# Breakout_05_08.net
KiCad netlist of a schematic drawn in EAGLE
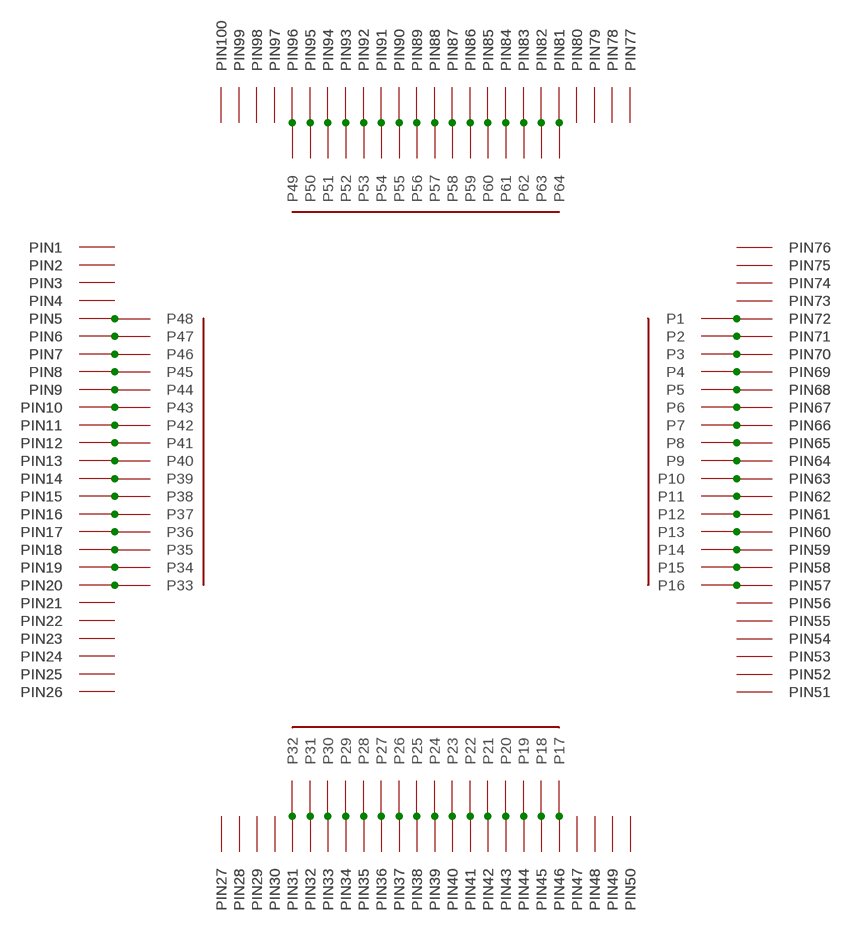
[diagram p0: schematic, sheet 1]

(export (version "E")
  (design (tool "Eeschema 10.0.6"))
  (components
    (comp (ref "U$1")
      (value "OUTTER_PADS_100PIN")
      (footprint "eagle-import:TQFP_100_PIN_DIN")
      (libsource (lib "eagle-import") (part "OUTTER_PADS_100PIN"))
    )
    (comp (ref "U$2")
      (value "SMT_64PIN_R")
      (footprint "eagle-import:TQFP_SMT_08MM")
      (libsource (lib "eagle-import") (part "SMT_64PIN_R"))
    )
    (comp (ref "U$3")
      (value "SMT_100PIN")
      (footprint "eagle-import:TQFP_SMT_05MM")
      (libsource (lib "eagle-import") (part "SMT_100PIN"))
    )
  )
  (nets
    (net (code "1") (name "Net-(U$1-PIN1)") (class "Default")
      (node (ref "U$1") (pin "P$101") (pinfunction "PIN1_P$101") (pintype "bidirectional"))
      (node (ref "U$3") (pin "P$1") (pinfunction "PIN1_P$1") (pintype "bidirectional"))
    )
    (net (code "2") (name "Net-(U$1-PIN2)") (class "Default")
      (node (ref "U$1") (pin "P$102") (pinfunction "PIN2_P$102") (pintype "bidirectional"))
      (node (ref "U$3") (pin "P$2") (pinfunction "PIN2_P$2") (pintype "bidirectional"))
    )
    (net (code "3") (name "Net-(U$1-PIN3)") (class "Default")
      (node (ref "U$1") (pin "P$103") (pinfunction "PIN3_P$103") (pintype "bidirectional"))
      (node (ref "U$3") (pin "P$3") (pinfunction "PIN3_P$3") (pintype "bidirectional"))
    )
    (net (code "4") (name "Net-(U$1-PIN4)") (class "Default")
      (node (ref "U$1") (pin "P$104") (pinfunction "PIN4_P$104") (pintype "bidirectional"))
      (node (ref "U$3") (pin "P$4") (pinfunction "PIN4_P$4") (pintype "bidirectional"))
    )
    (net (code "5") (name "Net-(U$1-PIN5)") (class "Default")
      (node (ref "U$1") (pin "P$105") (pinfunction "PIN5_P$105") (pintype "bidirectional"))
      (node (ref "U$2") (pin "P$49") (pinfunction "P48_P$49") (pintype "bidirectional"))
      (node (ref "U$3") (pin "P$5") (pinfunction "PIN5_P$5") (pintype "bidirectional"))
    )
    (net (code "6") (name "Net-(U$1-PIN6)") (class "Default")
      (node (ref "U$1") (pin "P$106") (pinfunction "PIN6_P$106") (pintype "bidirectional"))
      (node (ref "U$2") (pin "P$48") (pinfunction "P47_P$48") (pintype "bidirectional"))
      (node (ref "U$3") (pin "P$6") (pinfunction "PIN6_P$6") (pintype "bidirectional"))
    )
    (net (code "7") (name "Net-(U$1-PIN7)") (class "Default")
      (node (ref "U$1") (pin "P$107") (pinfunction "PIN7_P$107") (pintype "bidirectional"))
      (node (ref "U$2") (pin "P$47") (pinfunction "P46_P$47") (pintype "bidirectional"))
      (node (ref "U$3") (pin "P$7") (pinfunction "PIN7_P$7") (pintype "bidirectional"))
    )
    (net (code "8") (name "Net-(U$1-PIN8)") (class "Default")
      (node (ref "U$1") (pin "P$108") (pinfunction "PIN8_P$108") (pintype "bidirectional"))
      (node (ref "U$2") (pin "P$46") (pinfunction "P45_P$46") (pintype "bidirectional"))
      (node (ref "U$3") (pin "P$8") (pinfunction "PIN8_P$8") (pintype "bidirectional"))
    )
    (net (code "9") (name "Net-(U$1-PIN9)") (class "Default")
      (node (ref "U$1") (pin "P$109") (pinfunction "PIN9_P$109") (pintype "bidirectional"))
      (node (ref "U$2") (pin "P$45") (pinfunction "P44_P$45") (pintype "bidirectional"))
      (node (ref "U$3") (pin "P$9") (pinfunction "PIN9_P$9") (pintype "bidirectional"))
    )
    (net (code "10") (name "Net-(U$1-PIN10)") (class "Default")
      (node (ref "U$1") (pin "P$110") (pinfunction "PIN10_P$110") (pintype "bidirectional"))
      (node (ref "U$2") (pin "P$44") (pinfunction "P43_P$44") (pintype "bidirectional"))
      (node (ref "U$3") (pin "P$10") (pinfunction "PIN10_P$10") (pintype "bidirectional"))
    )
    (net (code "11") (name "Net-(U$1-PIN11)") (class "Default")
      (node (ref "U$1") (pin "P$111") (pinfunction "PIN11_P$111") (pintype "bidirectional"))
      (node (ref "U$2") (pin "P$43") (pinfunction "P42_P$43") (pintype "bidirectional"))
      (node (ref "U$3") (pin "P$11") (pinfunction "PIN11_P$11") (pintype "bidirectional"))
    )
    (net (code "12") (name "Net-(U$1-PIN12)") (class "Default")
      (node (ref "U$1") (pin "P$112") (pinfunction "PIN12_P$112") (pintype "bidirectional"))
      (node (ref "U$2") (pin "P$42") (pinfunction "P41_P$42") (pintype "bidirectional"))
      (node (ref "U$3") (pin "P$12") (pinfunction "PIN12_P$12") (pintype "bidirectional"))
    )
    (net (code "13") (name "Net-(U$1-PIN13)") (class "Default")
      (node (ref "U$1") (pin "P$113") (pinfunction "PIN13_P$113") (pintype "bidirectional"))
      (node (ref "U$2") (pin "P$41") (pinfunction "P40_P$41") (pintype "bidirectional"))
      (node (ref "U$3") (pin "P$13") (pinfunction "PIN13_P$13") (pintype "bidirectional"))
    )
    (net (code "14") (name "Net-(U$1-PIN14)") (class "Default")
      (node (ref "U$1") (pin "P$114") (pinfunction "PIN14_P$114") (pintype "bidirectional"))
      (node (ref "U$2") (pin "P$40") (pinfunction "P39_P$40") (pintype "bidirectional"))
      (node (ref "U$3") (pin "P$14") (pinfunction "PIN14_P$14") (pintype "bidirectional"))
    )
    (net (code "15") (name "Net-(U$1-PIN15)") (class "Default")
      (node (ref "U$1") (pin "P$115") (pinfunction "PIN15_P$115") (pintype "bidirectional"))
      (node (ref "U$2") (pin "P$39") (pinfunction "P38_P$39") (pintype "bidirectional"))
      (node (ref "U$3") (pin "P$15") (pinfunction "PIN15_P$15") (pintype "bidirectional"))
    )
    (net (code "16") (name "Net-(U$1-PIN16)") (class "Default")
      (node (ref "U$1") (pin "P$116") (pinfunction "PIN16_P$116") (pintype "bidirectional"))
      (node (ref "U$2") (pin "P$38") (pinfunction "P37_P$38") (pintype "bidirectional"))
      (node (ref "U$3") (pin "P$16") (pinfunction "PIN16_P$16") (pintype "bidirectional"))
    )
    (net (code "17") (name "Net-(U$1-PIN17)") (class "Default")
      (node (ref "U$1") (pin "P$117") (pinfunction "PIN17_P$117") (pintype "bidirectional"))
      (node (ref "U$2") (pin "P$37") (pinfunction "P36_P$37") (pintype "bidirectional"))
      (node (ref "U$3") (pin "P$17") (pinfunction "PIN17_P$17") (pintype "bidirectional"))
    )
    (net (code "18") (name "Net-(U$1-PIN18)") (class "Default")
      (node (ref "U$1") (pin "P$118") (pinfunction "PIN18_P$118") (pintype "bidirectional"))
      (node (ref "U$2") (pin "P$36") (pinfunction "P35_P$36") (pintype "bidirectional"))
      (node (ref "U$3") (pin "P$18") (pinfunction "PIN18_P$18") (pintype "bidirectional"))
    )
    (net (code "19") (name "Net-(U$1-PIN19)") (class "Default")
      (node (ref "U$1") (pin "P$119") (pinfunction "PIN19_P$119") (pintype "bidirectional"))
      (node (ref "U$2") (pin "P$35") (pinfunction "P34_P$35") (pintype "bidirectional"))
      (node (ref "U$3") (pin "P$19") (pinfunction "PIN19_P$19") (pintype "bidirectional"))
    )
    (net (code "20") (name "Net-(U$1-PIN20)") (class "Default")
      (node (ref "U$1") (pin "P$120") (pinfunction "PIN20_P$120") (pintype "bidirectional"))
      (node (ref "U$2") (pin "P$34") (pinfunction "P33_P$34") (pintype "bidirectional"))
      (node (ref "U$3") (pin "P$20") (pinfunction "PIN20_P$20") (pintype "bidirectional"))
    )
    (net (code "21") (name "Net-(U$1-PIN21)") (class "Default")
      (node (ref "U$1") (pin "P$121") (pinfunction "PIN21_P$121") (pintype "bidirectional"))
      (node (ref "U$3") (pin "P$21") (pinfunction "PIN21_P$21") (pintype "bidirectional"))
    )
    (net (code "22") (name "Net-(U$1-PIN22)") (class "Default")
      (node (ref "U$1") (pin "P$122") (pinfunction "PIN22_P$122") (pintype "bidirectional"))
      (node (ref "U$3") (pin "P$22") (pinfunction "PIN22_P$22") (pintype "bidirectional"))
    )
    (net (code "23") (name "Net-(U$1-PIN23)") (class "Default")
      (node (ref "U$1") (pin "P$123") (pinfunction "PIN23_P$123") (pintype "bidirectional"))
      (node (ref "U$3") (pin "P$23") (pinfunction "PIN23_P$23") (pintype "bidirectional"))
    )
    (net (code "24") (name "Net-(U$1-PIN24)") (class "Default")
      (node (ref "U$1") (pin "P$124") (pinfunction "PIN24_P$124") (pintype "bidirectional"))
      (node (ref "U$3") (pin "P$24") (pinfunction "PIN24_P$24") (pintype "bidirectional"))
    )
    (net (code "25") (name "Net-(U$1-PIN25)") (class "Default")
      (node (ref "U$1") (pin "P$125") (pinfunction "PIN25_P$125") (pintype "bidirectional"))
      (node (ref "U$3") (pin "P$25") (pinfunction "PIN25_P$25") (pintype "bidirectional"))
    )
    (net (code "26") (name "Net-(U$1-PIN26)") (class "Default")
      (node (ref "U$1") (pin "P$126") (pinfunction "PIN26_P$126") (pintype "bidirectional"))
      (node (ref "U$3") (pin "P$26") (pinfunction "PIN26_P$26") (pintype "bidirectional"))
    )
    (net (code "27") (name "Net-(U$1-PIN27)") (class "Default")
      (node (ref "U$1") (pin "P$127") (pinfunction "PIN27_P$127") (pintype "bidirectional"))
      (node (ref "U$3") (pin "P$27") (pinfunction "PIN27_P$27") (pintype "bidirectional"))
    )
    (net (code "28") (name "Net-(U$1-PIN28)") (class "Default")
      (node (ref "U$1") (pin "P$128") (pinfunction "PIN28_P$128") (pintype "bidirectional"))
      (node (ref "U$3") (pin "P$28") (pinfunction "PIN28_P$28") (pintype "bidirectional"))
    )
    (net (code "29") (name "Net-(U$1-PIN29)") (class "Default")
      (node (ref "U$1") (pin "P$129") (pinfunction "PIN29_P$129") (pintype "bidirectional"))
      (node (ref "U$3") (pin "P$29") (pinfunction "PIN29_P$29") (pintype "bidirectional"))
    )
    (net (code "30") (name "Net-(U$1-PIN30)") (class "Default")
      (node (ref "U$1") (pin "P$130") (pinfunction "PIN30_P$130") (pintype "bidirectional"))
      (node (ref "U$3") (pin "P$30") (pinfunction "PIN30_P$30") (pintype "bidirectional"))
    )
    (net (code "31") (name "Net-(U$1-PIN31)") (class "Default")
      (node (ref "U$1") (pin "P$131") (pinfunction "PIN31_P$131") (pintype "bidirectional"))
      (node (ref "U$2") (pin "P$33") (pinfunction "P32_P$33") (pintype "bidirectional"))
      (node (ref "U$3") (pin "P$31") (pinfunction "PIN31_P$31") (pintype "bidirectional"))
    )
    (net (code "32") (name "Net-(U$1-PIN32)") (class "Default")
      (node (ref "U$1") (pin "P$132") (pinfunction "PIN32_P$132") (pintype "bidirectional"))
      (node (ref "U$2") (pin "P$32") (pinfunction "P31_P$32") (pintype "bidirectional"))
      (node (ref "U$3") (pin "P$32") (pinfunction "PIN32_P$32") (pintype "bidirectional"))
    )
    (net (code "33") (name "Net-(U$1-PIN33)") (class "Default")
      (node (ref "U$1") (pin "P$133") (pinfunction "PIN33_P$133") (pintype "bidirectional"))
      (node (ref "U$2") (pin "P$31") (pinfunction "P30_P$31") (pintype "bidirectional"))
      (node (ref "U$3") (pin "P$33") (pinfunction "PIN33_P$33") (pintype "bidirectional"))
    )
    (net (code "34") (name "Net-(U$1-PIN34)") (class "Default")
      (node (ref "U$1") (pin "P$134") (pinfunction "PIN34_P$134") (pintype "bidirectional"))
      (node (ref "U$2") (pin "P$30") (pinfunction "P29_P$30") (pintype "bidirectional"))
      (node (ref "U$3") (pin "P$34") (pinfunction "PIN34_P$34") (pintype "bidirectional"))
    )
    (net (code "35") (name "Net-(U$1-PIN35)") (class "Default")
      (node (ref "U$1") (pin "P$135") (pinfunction "PIN35_P$135") (pintype "bidirectional"))
      (node (ref "U$2") (pin "P$29") (pinfunction "P28_P$29") (pintype "bidirectional"))
      (node (ref "U$3") (pin "P$35") (pinfunction "PIN35_P$35") (pintype "bidirectional"))
    )
    (net (code "36") (name "Net-(U$1-PIN36)") (class "Default")
      (node (ref "U$1") (pin "P$136") (pinfunction "PIN36_P$136") (pintype "bidirectional"))
      (node (ref "U$2") (pin "P$28") (pinfunction "P27_P$28") (pintype "bidirectional"))
      (node (ref "U$3") (pin "P$36") (pinfunction "PIN36_P$36") (pintype "bidirectional"))
    )
    (net (code "37") (name "Net-(U$1-PIN37)") (class "Default")
      (node (ref "U$1") (pin "P$137") (pinfunction "PIN37_P$137") (pintype "bidirectional"))
      (node (ref "U$2") (pin "P$27") (pinfunction "P26_P$27") (pintype "bidirectional"))
      (node (ref "U$3") (pin "P$37") (pinfunction "PIN37_P$37") (pintype "bidirectional"))
    )
    (net (code "38") (name "Net-(U$1-PIN38)") (class "Default")
      (node (ref "U$1") (pin "P$138") (pinfunction "PIN38_P$138") (pintype "bidirectional"))
      (node (ref "U$2") (pin "P$25") (pinfunction "P25_P$25") (pintype "bidirectional"))
      (node (ref "U$3") (pin "P$38") (pinfunction "PIN38_P$38") (pintype "bidirectional"))
    )
    (net (code "39") (name "Net-(U$1-PIN39)") (class "Default")
      (node (ref "U$1") (pin "P$139") (pinfunction "PIN39_P$139") (pintype "bidirectional"))
      (node (ref "U$2") (pin "P$24") (pinfunction "P24_P$24") (pintype "bidirectional"))
      (node (ref "U$3") (pin "P$39") (pinfunction "PIN39_P$39") (pintype "bidirectional"))
    )
    (net (code "40") (name "Net-(U$1-PIN40)") (class "Default")
      (node (ref "U$1") (pin "P$140") (pinfunction "PIN40_P$140") (pintype "bidirectional"))
      (node (ref "U$2") (pin "P$23") (pinfunction "P23_P$23") (pintype "bidirectional"))
      (node (ref "U$3") (pin "P$40") (pinfunction "PIN40_P$40") (pintype "bidirectional"))
    )
    (net (code "41") (name "Net-(U$1-PIN41)") (class "Default")
      (node (ref "U$1") (pin "P$141") (pinfunction "PIN41_P$141") (pintype "bidirectional"))
      (node (ref "U$2") (pin "P$22") (pinfunction "P22_P$22") (pintype "bidirectional"))
      (node (ref "U$3") (pin "P$41") (pinfunction "PIN41_P$41") (pintype "bidirectional"))
    )
    (net (code "42") (name "Net-(U$1-PIN42)") (class "Default")
      (node (ref "U$1") (pin "P$142") (pinfunction "PIN42_P$142") (pintype "bidirectional"))
      (node (ref "U$2") (pin "P$21") (pinfunction "P21_P$21") (pintype "bidirectional"))
      (node (ref "U$3") (pin "P$42") (pinfunction "PIN42_P$42") (pintype "bidirectional"))
    )
    (net (code "43") (name "Net-(U$1-PIN43)") (class "Default")
      (node (ref "U$1") (pin "P$143") (pinfunction "PIN43_P$143") (pintype "bidirectional"))
      (node (ref "U$2") (pin "P$20") (pinfunction "P20_P$20") (pintype "bidirectional"))
      (node (ref "U$3") (pin "P$43") (pinfunction "PIN43_P$43") (pintype "bidirectional"))
    )
    (net (code "44") (name "Net-(U$1-PIN44)") (class "Default")
      (node (ref "U$1") (pin "P$144") (pinfunction "PIN44_P$144") (pintype "bidirectional"))
      (node (ref "U$2") (pin "P$19") (pinfunction "P19_P$19") (pintype "bidirectional"))
      (node (ref "U$3") (pin "P$44") (pinfunction "PIN44_P$44") (pintype "bidirectional"))
    )
    (net (code "45") (name "Net-(U$1-PIN45)") (class "Default")
      (node (ref "U$1") (pin "P$145") (pinfunction "PIN45_P$145") (pintype "bidirectional"))
      (node (ref "U$2") (pin "P$18") (pinfunction "P18_P$18") (pintype "bidirectional"))
      (node (ref "U$3") (pin "P$45") (pinfunction "PIN45_P$45") (pintype "bidirectional"))
    )
    (net (code "46") (name "Net-(U$1-PIN46)") (class "Default")
      (node (ref "U$1") (pin "P$146") (pinfunction "PIN46_P$146") (pintype "bidirectional"))
      (node (ref "U$2") (pin "P$17") (pinfunction "P17_P$17") (pintype "bidirectional"))
      (node (ref "U$3") (pin "P$46") (pinfunction "PIN46_P$46") (pintype "bidirectional"))
    )
    (net (code "47") (name "Net-(U$1-PIN47)") (class "Default")
      (node (ref "U$1") (pin "P$147") (pinfunction "PIN47_P$147") (pintype "bidirectional"))
      (node (ref "U$3") (pin "P$47") (pinfunction "PIN47_P$47") (pintype "bidirectional"))
    )
    (net (code "48") (name "Net-(U$1-PIN48)") (class "Default")
      (node (ref "U$1") (pin "P$148") (pinfunction "PIN48_P$148") (pintype "bidirectional"))
      (node (ref "U$3") (pin "P$48") (pinfunction "PIN48_P$48") (pintype "bidirectional"))
    )
    (net (code "49") (name "Net-(U$1-PIN49)") (class "Default")
      (node (ref "U$1") (pin "P$149") (pinfunction "PIN49_P$149") (pintype "bidirectional"))
      (node (ref "U$3") (pin "P$49") (pinfunction "PIN49_P$49") (pintype "bidirectional"))
    )
    (net (code "50") (name "Net-(U$1-PIN50)") (class "Default")
      (node (ref "U$1") (pin "P$150") (pinfunction "PIN50_P$150") (pintype "bidirectional"))
      (node (ref "U$3") (pin "P$50") (pinfunction "PIN50_P$50") (pintype "bidirectional"))
    )
    (net (code "51") (name "Net-(U$1-PIN51)") (class "Default")
      (node (ref "U$1") (pin "P$151") (pinfunction "PIN51_P$151") (pintype "bidirectional"))
      (node (ref "U$3") (pin "P$51") (pinfunction "PIN51_P$51") (pintype "bidirectional"))
    )
    (net (code "52") (name "Net-(U$1-PIN52)") (class "Default")
      (node (ref "U$1") (pin "P$152") (pinfunction "PIN52_P$152") (pintype "bidirectional"))
      (node (ref "U$3") (pin "P$52") (pinfunction "PIN52_P$52") (pintype "bidirectional"))
    )
    (net (code "53") (name "Net-(U$1-PIN53)") (class "Default")
      (node (ref "U$1") (pin "P$153") (pinfunction "PIN53_P$153") (pintype "bidirectional"))
      (node (ref "U$3") (pin "P$53") (pinfunction "PIN53_P$53") (pintype "bidirectional"))
    )
    (net (code "54") (name "Net-(U$1-PIN54)") (class "Default")
      (node (ref "U$1") (pin "P$154") (pinfunction "PIN54_P$154") (pintype "bidirectional"))
      (node (ref "U$3") (pin "P$54") (pinfunction "PIN54_P$54") (pintype "bidirectional"))
    )
    (net (code "55") (name "Net-(U$1-PIN55)") (class "Default")
      (node (ref "U$1") (pin "P$155") (pinfunction "PIN55_P$155") (pintype "bidirectional"))
      (node (ref "U$3") (pin "P$55") (pinfunction "PIN55_P$55") (pintype "bidirectional"))
    )
    (net (code "56") (name "Net-(U$1-PIN56)") (class "Default")
      (node (ref "U$1") (pin "P$156") (pinfunction "PIN56_P$156") (pintype "bidirectional"))
      (node (ref "U$3") (pin "P$56") (pinfunction "PIN56_P$56") (pintype "bidirectional"))
    )
    (net (code "57") (name "Net-(U$1-PIN57)") (class "Default")
      (node (ref "U$1") (pin "P$157") (pinfunction "PIN57_P$157") (pintype "bidirectional"))
      (node (ref "U$2") (pin "P$16") (pinfunction "P16_P$16") (pintype "bidirectional"))
      (node (ref "U$3") (pin "P$57") (pinfunction "PIN57_P$57") (pintype "bidirectional"))
    )
    (net (code "58") (name "Net-(U$1-PIN58)") (class "Default")
      (node (ref "U$1") (pin "P$158") (pinfunction "PIN58_P$158") (pintype "bidirectional"))
      (node (ref "U$2") (pin "P$15") (pinfunction "P15_P$15") (pintype "bidirectional"))
      (node (ref "U$3") (pin "P$58") (pinfunction "PIN58_P$58") (pintype "bidirectional"))
    )
    (net (code "59") (name "Net-(U$1-PIN59)") (class "Default")
      (node (ref "U$1") (pin "P$159") (pinfunction "PIN59_P$159") (pintype "bidirectional"))
      (node (ref "U$2") (pin "P$14") (pinfunction "P14_P$14") (pintype "bidirectional"))
      (node (ref "U$3") (pin "P$59") (pinfunction "PIN59_P$59") (pintype "bidirectional"))
    )
    (net (code "60") (name "Net-(U$1-PIN60)") (class "Default")
      (node (ref "U$1") (pin "P$160") (pinfunction "PIN60_P$160") (pintype "bidirectional"))
      (node (ref "U$2") (pin "P$13") (pinfunction "P13_P$13") (pintype "bidirectional"))
      (node (ref "U$3") (pin "P$60") (pinfunction "PIN60_P$60") (pintype "bidirectional"))
    )
    (net (code "61") (name "Net-(U$1-PIN61)") (class "Default")
      (node (ref "U$1") (pin "P$161") (pinfunction "PIN61_P$161") (pintype "bidirectional"))
      (node (ref "U$2") (pin "P$12") (pinfunction "P12_P$12") (pintype "bidirectional"))
      (node (ref "U$3") (pin "P$61") (pinfunction "PIN61_P$61") (pintype "bidirectional"))
    )
    (net (code "62") (name "Net-(U$1-PIN62)") (class "Default")
      (node (ref "U$1") (pin "P$162") (pinfunction "PIN62_P$162") (pintype "bidirectional"))
      (node (ref "U$2") (pin "P$11") (pinfunction "P11_P$11") (pintype "bidirectional"))
      (node (ref "U$3") (pin "P$62") (pinfunction "PIN62_P$62") (pintype "bidirectional"))
    )
    (net (code "63") (name "Net-(U$1-PIN63)") (class "Default")
      (node (ref "U$1") (pin "P$163") (pinfunction "PIN63_P$163") (pintype "bidirectional"))
      (node (ref "U$2") (pin "P$10") (pinfunction "P10_P$10") (pintype "bidirectional"))
      (node (ref "U$3") (pin "P$63") (pinfunction "PIN63_P$63") (pintype "bidirectional"))
    )
    (net (code "64") (name "Net-(U$1-PIN64)") (class "Default")
      (node (ref "U$1") (pin "P$164") (pinfunction "PIN64_P$164") (pintype "bidirectional"))
      (node (ref "U$2") (pin "P$9") (pinfunction "P9_P$9") (pintype "bidirectional"))
      (node (ref "U$3") (pin "P$64") (pinfunction "PIN64_P$64") (pintype "bidirectional"))
    )
    (net (code "65") (name "Net-(U$1-PIN65)") (class "Default")
      (node (ref "U$1") (pin "P$165") (pinfunction "PIN65_P$165") (pintype "bidirectional"))
      (node (ref "U$2") (pin "P$8") (pinfunction "P8_P$8") (pintype "bidirectional"))
      (node (ref "U$3") (pin "P$65") (pinfunction "PIN65_P$65") (pintype "bidirectional"))
    )
    (net (code "66") (name "Net-(U$1-PIN66)") (class "Default")
      (node (ref "U$1") (pin "P$166") (pinfunction "PIN66_P$166") (pintype "bidirectional"))
      (node (ref "U$2") (pin "P$7") (pinfunction "P7_P$7") (pintype "bidirectional"))
      (node (ref "U$3") (pin "P$66") (pinfunction "PIN66_P$66") (pintype "bidirectional"))
    )
    (net (code "67") (name "Net-(U$1-PIN67)") (class "Default")
      (node (ref "U$1") (pin "P$167") (pinfunction "PIN67_P$167") (pintype "bidirectional"))
      (node (ref "U$2") (pin "P$6") (pinfunction "P6_P$6") (pintype "bidirectional"))
      (node (ref "U$3") (pin "P$67") (pinfunction "PIN67_P$67") (pintype "bidirectional"))
    )
    (net (code "68") (name "Net-(U$1-PIN68)") (class "Default")
      (node (ref "U$1") (pin "P$168") (pinfunction "PIN68_P$168") (pintype "bidirectional"))
      (node (ref "U$2") (pin "P$5") (pinfunction "P5_P$5") (pintype "bidirectional"))
      (node (ref "U$3") (pin "P$68") (pinfunction "PIN68_P$68") (pintype "bidirectional"))
    )
    (net (code "69") (name "Net-(U$1-PIN69)") (class "Default")
      (node (ref "U$1") (pin "P$169") (pinfunction "PIN69_P$169") (pintype "bidirectional"))
      (node (ref "U$2") (pin "P$4") (pinfunction "P4_P$4") (pintype "bidirectional"))
      (node (ref "U$3") (pin "P$69") (pinfunction "PIN69_P$69") (pintype "bidirectional"))
    )
    (net (code "70") (name "Net-(U$1-PIN70)") (class "Default")
      (node (ref "U$1") (pin "P$170") (pinfunction "PIN70_P$170") (pintype "bidirectional"))
      (node (ref "U$2") (pin "P$3") (pinfunction "P3_P$3") (pintype "bidirectional"))
      (node (ref "U$3") (pin "P$70") (pinfunction "PIN70_P$70") (pintype "bidirectional"))
    )
    (net (code "71") (name "Net-(U$1-PIN71)") (class "Default")
      (node (ref "U$1") (pin "P$171") (pinfunction "PIN71_P$171") (pintype "bidirectional"))
      (node (ref "U$2") (pin "P$2") (pinfunction "P2_P$2") (pintype "bidirectional"))
      (node (ref "U$3") (pin "P$71") (pinfunction "PIN71_P$71") (pintype "bidirectional"))
    )
    (net (code "72") (name "Net-(U$1-PIN72)") (class "Default")
      (node (ref "U$1") (pin "P$172") (pinfunction "PIN72_P$172") (pintype "bidirectional"))
      (node (ref "U$2") (pin "P$1") (pinfunction "P1_P$1") (pintype "bidirectional"))
      (node (ref "U$3") (pin "P$72") (pinfunction "PIN72_P$72") (pintype "bidirectional"))
    )
    (net (code "73") (name "Net-(U$1-PIN73)") (class "Default")
      (node (ref "U$1") (pin "P$173") (pinfunction "PIN73_P$173") (pintype "bidirectional"))
      (node (ref "U$3") (pin "P$73") (pinfunction "PIN73_P$73") (pintype "bidirectional"))
    )
    (net (code "74") (name "Net-(U$1-PIN74)") (class "Default")
      (node (ref "U$1") (pin "P$174") (pinfunction "PIN74_P$174") (pintype "bidirectional"))
      (node (ref "U$3") (pin "P$74") (pinfunction "PIN74_P$74") (pintype "bidirectional"))
    )
    (net (code "75") (name "Net-(U$1-PIN75)") (class "Default")
      (node (ref "U$1") (pin "P$175") (pinfunction "PIN75_P$175") (pintype "bidirectional"))
      (node (ref "U$3") (pin "P$75") (pinfunction "PIN75_P$75") (pintype "bidirectional"))
    )
    (net (code "76") (name "Net-(U$1-PIN76)") (class "Default")
      (node (ref "U$1") (pin "P$176") (pinfunction "PIN76_P$176") (pintype "bidirectional"))
      (node (ref "U$3") (pin "P$76") (pinfunction "PIN76_P$76") (pintype "bidirectional"))
    )
    (net (code "77") (name "Net-(U$1-PIN77)") (class "Default")
      (node (ref "U$1") (pin "P$177") (pinfunction "PIN77_P$177") (pintype "bidirectional"))
      (node (ref "U$3") (pin "P$77") (pinfunction "PIN77_P$77") (pintype "bidirectional"))
    )
    (net (code "78") (name "Net-(U$1-PIN78)") (class "Default")
      (node (ref "U$1") (pin "P$178") (pinfunction "PIN78_P$178") (pintype "bidirectional"))
      (node (ref "U$3") (pin "P$78") (pinfunction "PIN78_P$78") (pintype "bidirectional"))
    )
    (net (code "79") (name "Net-(U$1-PIN79)") (class "Default")
      (node (ref "U$1") (pin "P$179") (pinfunction "PIN79_P$179") (pintype "bidirectional"))
      (node (ref "U$3") (pin "P$79") (pinfunction "PIN79_P$79") (pintype "bidirectional"))
    )
    (net (code "80") (name "Net-(U$1-PIN80)") (class "Default")
      (node (ref "U$1") (pin "P$180") (pinfunction "PIN80_P$180") (pintype "bidirectional"))
      (node (ref "U$3") (pin "P$80") (pinfunction "PIN80_P$80") (pintype "bidirectional"))
    )
    (net (code "81") (name "Net-(U$1-PIN81)") (class "Default")
      (node (ref "U$1") (pin "P$181") (pinfunction "PIN81_P$181") (pintype "bidirectional"))
      (node (ref "U$2") (pin "P$65") (pinfunction "P64_P$65") (pintype "bidirectional"))
      (node (ref "U$3") (pin "P$81") (pinfunction "PIN81_P$81") (pintype "bidirectional"))
    )
    (net (code "82") (name "Net-(U$1-PIN82)") (class "Default")
      (node (ref "U$1") (pin "P$182") (pinfunction "PIN82_P$182") (pintype "bidirectional"))
      (node (ref "U$2") (pin "P$64") (pinfunction "P63_P$64") (pintype "bidirectional"))
      (node (ref "U$3") (pin "P$82") (pinfunction "PIN82_P$82") (pintype "bidirectional"))
    )
    (net (code "83") (name "Net-(U$1-PIN83)") (class "Default")
      (node (ref "U$1") (pin "P$183") (pinfunction "PIN83_P$183") (pintype "bidirectional"))
      (node (ref "U$2") (pin "P$63") (pinfunction "P62_P$63") (pintype "bidirectional"))
      (node (ref "U$3") (pin "P$83") (pinfunction "PIN83_P$83") (pintype "bidirectional"))
    )
    (net (code "84") (name "Net-(U$1-PIN84)") (class "Default")
      (node (ref "U$1") (pin "P$184") (pinfunction "PIN84_P$184") (pintype "bidirectional"))
      (node (ref "U$2") (pin "P$62") (pinfunction "P61_P$62") (pintype "bidirectional"))
      (node (ref "U$3") (pin "P$84") (pinfunction "PIN84_P$84") (pintype "bidirectional"))
    )
    (net (code "85") (name "Net-(U$1-PIN85)") (class "Default")
      (node (ref "U$1") (pin "P$185") (pinfunction "PIN85_P$185") (pintype "bidirectional"))
      (node (ref "U$2") (pin "P$61") (pinfunction "P60_P$61") (pintype "bidirectional"))
      (node (ref "U$3") (pin "P$85") (pinfunction "PIN85_P$85") (pintype "bidirectional"))
    )
    (net (code "86") (name "Net-(U$1-PIN86)") (class "Default")
      (node (ref "U$1") (pin "P$186") (pinfunction "PIN86_P$186") (pintype "bidirectional"))
      (node (ref "U$2") (pin "P$60") (pinfunction "P59_P$60") (pintype "bidirectional"))
      (node (ref "U$3") (pin "P$86") (pinfunction "PIN86_P$86") (pintype "bidirectional"))
    )
    (net (code "87") (name "Net-(U$1-PIN87)") (class "Default")
      (node (ref "U$1") (pin "P$187") (pinfunction "PIN87_P$187") (pintype "bidirectional"))
      (node (ref "U$2") (pin "P$59") (pinfunction "P58_P$59") (pintype "bidirectional"))
      (node (ref "U$3") (pin "P$87") (pinfunction "PIN87_P$87") (pintype "bidirectional"))
    )
    (net (code "88") (name "Net-(U$1-PIN88)") (class "Default")
      (node (ref "U$1") (pin "P$188") (pinfunction "PIN88_P$188") (pintype "bidirectional"))
      (node (ref "U$2") (pin "P$58") (pinfunction "P57_P$58") (pintype "bidirectional"))
      (node (ref "U$3") (pin "P$88") (pinfunction "PIN88_P$88") (pintype "bidirectional"))
    )
    (net (code "89") (name "Net-(U$1-PIN89)") (class "Default")
      (node (ref "U$1") (pin "P$189") (pinfunction "PIN89_P$189") (pintype "bidirectional"))
      (node (ref "U$2") (pin "P$57") (pinfunction "P56_P$57") (pintype "bidirectional"))
      (node (ref "U$3") (pin "P$89") (pinfunction "PIN89_P$89") (pintype "bidirectional"))
    )
    (net (code "90") (name "Net-(U$1-PIN90)") (class "Default")
      (node (ref "U$1") (pin "P$190") (pinfunction "PIN90_P$190") (pintype "bidirectional"))
      (node (ref "U$2") (pin "P$56") (pinfunction "P55_P$56") (pintype "bidirectional"))
      (node (ref "U$3") (pin "P$90") (pinfunction "PIN90_P$90") (pintype "bidirectional"))
    )
    (net (code "91") (name "Net-(U$1-PIN91)") (class "Default")
      (node (ref "U$1") (pin "P$191") (pinfunction "PIN91_P$191") (pintype "bidirectional"))
      (node (ref "U$2") (pin "P$55") (pinfunction "P54_P$55") (pintype "bidirectional"))
      (node (ref "U$3") (pin "P$91") (pinfunction "PIN91_P$91") (pintype "bidirectional"))
    )
    (net (code "92") (name "Net-(U$1-PIN92)") (class "Default")
      (node (ref "U$1") (pin "P$192") (pinfunction "PIN92_P$192") (pintype "bidirectional"))
      (node (ref "U$2") (pin "P$54") (pinfunction "P53_P$54") (pintype "bidirectional"))
      (node (ref "U$3") (pin "P$92") (pinfunction "PIN92_P$92") (pintype "bidirectional"))
    )
    (net (code "93") (name "Net-(U$1-PIN93)") (class "Default")
      (node (ref "U$1") (pin "P$193") (pinfunction "PIN93_P$193") (pintype "bidirectional"))
      (node (ref "U$2") (pin "P$53") (pinfunction "P52_P$53") (pintype "bidirectional"))
      (node (ref "U$3") (pin "P$93") (pinfunction "PIN93_P$93") (pintype "bidirectional"))
    )
    (net (code "94") (name "Net-(U$1-PIN94)") (class "Default")
      (node (ref "U$1") (pin "P$194") (pinfunction "PIN94_P$194") (pintype "bidirectional"))
      (node (ref "U$2") (pin "P$52") (pinfunction "P51_P$52") (pintype "bidirectional"))
      (node (ref "U$3") (pin "P$94") (pinfunction "PIN94_P$94") (pintype "bidirectional"))
    )
    (net (code "95") (name "Net-(U$1-PIN95)") (class "Default")
      (node (ref "U$1") (pin "P$195") (pinfunction "PIN95_P$195") (pintype "bidirectional"))
      (node (ref "U$2") (pin "P$51") (pinfunction "P50_P$51") (pintype "bidirectional"))
      (node (ref "U$3") (pin "P$95") (pinfunction "PIN95_P$95") (pintype "bidirectional"))
    )
    (net (code "96") (name "Net-(U$1-PIN96)") (class "Default")
      (node (ref "U$1") (pin "P$196") (pinfunction "PIN96_P$196") (pintype "bidirectional"))
      (node (ref "U$2") (pin "P$50") (pinfunction "P49_P$50") (pintype "bidirectional"))
      (node (ref "U$3") (pin "P$96") (pinfunction "PIN96_P$96") (pintype "bidirectional"))
    )
    (net (code "97") (name "Net-(U$1-PIN97)") (class "Default")
      (node (ref "U$1") (pin "P$197") (pinfunction "PIN97_P$197") (pintype "bidirectional"))
      (node (ref "U$3") (pin "P$97") (pinfunction "PIN97_P$97") (pintype "bidirectional"))
    )
    (net (code "98") (name "Net-(U$1-PIN98)") (class "Default")
      (node (ref "U$1") (pin "P$198") (pinfunction "PIN98_P$198") (pintype "bidirectional"))
      (node (ref "U$3") (pin "P$98") (pinfunction "PIN98_P$98") (pintype "bidirectional"))
    )
    (net (code "99") (name "Net-(U$1-PIN99)") (class "Default")
      (node (ref "U$1") (pin "P$199") (pinfunction "PIN99_P$199") (pintype "bidirectional"))
      (node (ref "U$3") (pin "P$99") (pinfunction "PIN99_P$99") (pintype "bidirectional"))
    )
    (net (code "100") (name "Net-(U$1-PIN100)") (class "Default")
      (node (ref "U$1") (pin "P$200") (pinfunction "PIN100_P$200") (pintype "bidirectional"))
      (node (ref "U$3") (pin "P$100") (pinfunction "PIN100_P$100") (pintype "bidirectional"))
    )
  )
)
